# Header.net
KiCad netlist of a schematic drawn in Altium Designer
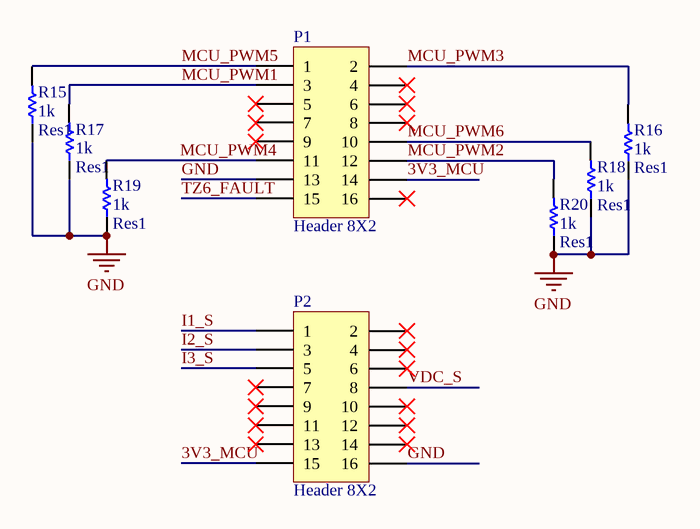
[diagram p0: Header.SchDoc]

(export (version "E")
  (design (tool "Eeschema 10.0.6"))
  (components
    (comp (ref "P1")
      (value "Header 8X2")
      (footprint "HDR2X8")
      (description "Header, 8-Pin, Dual row")
      (fields (field (name "PUBLISHER") "Altium Limited"))
      (libsource (lib "Miscellaneous Connectors") (part "Header 8X2"))
    )
    (comp (ref "P2")
      (value "Header 8X2")
      (footprint "HDR2X8")
      (description "Header, 8-Pin, Dual row")
      (fields (field (name "PUBLISHER") "Altium Limited"))
      (libsource (lib "Miscellaneous Connectors") (part "Header 8X2"))
    )
    (comp (ref "R15")
      (value "Res1")
      (footprint "AXIAL-0.4")
      (description "Resistor")
      (fields (field (name "ALTIUM_VALUE") "1k") (field (name "PUBLISHER") "Altium Limited"))
      (libsource (lib "Miscellaneous Devices") (part "Res1"))
    )
    (comp (ref "R16")
      (value "Res1")
      (footprint "AXIAL-0.4")
      (description "Resistor")
      (fields (field (name "ALTIUM_VALUE") "1k") (field (name "PUBLISHER") "Altium Limited"))
      (libsource (lib "Miscellaneous Devices") (part "Res1"))
    )
    (comp (ref "R17")
      (value "Res1")
      (footprint "AXIAL-0.4")
      (description "Resistor")
      (fields (field (name "ALTIUM_VALUE") "1k") (field (name "PUBLISHER") "Altium Limited"))
      (libsource (lib "Miscellaneous Devices") (part "Res1"))
    )
    (comp (ref "R18")
      (value "Res1")
      (footprint "AXIAL-0.4")
      (description "Resistor")
      (fields (field (name "ALTIUM_VALUE") "1k") (field (name "PUBLISHER") "Altium Limited"))
      (libsource (lib "Miscellaneous Devices") (part "Res1"))
    )
    (comp (ref "R19")
      (value "Res1")
      (footprint "AXIAL-0.4")
      (description "Resistor")
      (fields (field (name "ALTIUM_VALUE") "1k") (field (name "PUBLISHER") "Altium Limited"))
      (libsource (lib "Miscellaneous Devices") (part "Res1"))
    )
    (comp (ref "R20")
      (value "Res1")
      (footprint "AXIAL-0.4")
      (description "Resistor")
      (fields (field (name "ALTIUM_VALUE") "1k") (field (name "PUBLISHER") "Altium Limited"))
      (libsource (lib "Miscellaneous Devices") (part "Res1"))
    )
  )
  (nets
    (net (code "1") (name "/3V3_MCU") (class "Default")
      (node (ref "P1") (pin "14") (pinfunction "14_14") (pintype "passive"))
      (node (ref "P2") (pin "15") (pinfunction "15_15") (pintype "passive"))
    )
    (net (code "2") (name "/I1_S") (class "Default")
      (node (ref "P2") (pin "1") (pinfunction "1_1") (pintype "passive"))
    )
    (net (code "3") (name "/I2_S") (class "Default")
      (node (ref "P2") (pin "3") (pinfunction "3_3") (pintype "passive"))
    )
    (net (code "4") (name "/I3_S") (class "Default")
      (node (ref "P2") (pin "5") (pinfunction "5_5") (pintype "passive"))
    )
    (net (code "5") (name "/MCU_PWM1") (class "Default")
      (node (ref "P1") (pin "3") (pinfunction "3_3") (pintype "passive"))
      (node (ref "R17") (pin "2") (pinfunction "2_2") (pintype "passive"))
    )
    (net (code "6") (name "/MCU_PWM2") (class "Default")
      (node (ref "P1") (pin "12") (pinfunction "12_12") (pintype "passive"))
      (node (ref "R20") (pin "2") (pinfunction "2_2") (pintype "passive"))
    )
    (net (code "7") (name "/MCU_PWM3") (class "Default")
      (node (ref "P1") (pin "2") (pinfunction "2_2") (pintype "passive"))
      (node (ref "R16") (pin "2") (pinfunction "2_2") (pintype "passive"))
    )
    (net (code "8") (name "/MCU_PWM4") (class "Default")
      (node (ref "P1") (pin "11") (pinfunction "11_11") (pintype "passive"))
      (node (ref "R19") (pin "2") (pinfunction "2_2") (pintype "passive"))
    )
    (net (code "9") (name "/MCU_PWM5") (class "Default")
      (node (ref "P1") (pin "1") (pinfunction "1_1") (pintype "passive"))
      (node (ref "R15") (pin "2") (pinfunction "2_2") (pintype "passive"))
    )
    (net (code "10") (name "/MCU_PWM6") (class "Default")
      (node (ref "P1") (pin "10") (pinfunction "10_10") (pintype "passive"))
      (node (ref "R18") (pin "2") (pinfunction "2_2") (pintype "passive"))
    )
    (net (code "11") (name "/TZ6_FAULT") (class "Default")
      (node (ref "P1") (pin "15") (pinfunction "15_15") (pintype "passive"))
    )
    (net (code "12") (name "/VDC_S") (class "Default")
      (node (ref "P2") (pin "8") (pinfunction "8_8") (pintype "passive"))
    )
    (net (code "13") (name "GND") (class "Default")
      (node (ref "P1") (pin "13") (pinfunction "13_13") (pintype "passive"))
      (node (ref "P2") (pin "16") (pinfunction "16_16") (pintype "passive"))
      (node (ref "R15") (pin "1") (pinfunction "1_1") (pintype "passive"))
      (node (ref "R16") (pin "1") (pinfunction "1_1") (pintype "passive"))
      (node (ref "R17") (pin "1") (pinfunction "1_1") (pintype "passive"))
      (node (ref "R18") (pin "1") (pinfunction "1_1") (pintype "passive"))
      (node (ref "R19") (pin "1") (pinfunction "1_1") (pintype "passive"))
      (node (ref "R20") (pin "1") (pinfunction "1_1") (pintype "passive"))
    )
    (net (code "14") (name "unconnected-(P1-Pad4)") (class "Default")
      (node (ref "P1") (pin "4") (pinfunction "4_4") (pintype "passive+no_connect"))
    )
    (net (code "15") (name "unconnected-(P1-Pad5)") (class "Default")
      (node (ref "P1") (pin "5") (pinfunction "5_5") (pintype "passive+no_connect"))
    )
    (net (code "16") (name "unconnected-(P1-Pad6)") (class "Default")
      (node (ref "P1") (pin "6") (pinfunction "6_6") (pintype "passive+no_connect"))
    )
    (net (code "17") (name "unconnected-(P1-Pad7)") (class "Default")
      (node (ref "P1") (pin "7") (pinfunction "7_7") (pintype "passive+no_connect"))
    )
    (net (code "18") (name "unconnected-(P1-Pad8)") (class "Default")
      (node (ref "P1") (pin "8") (pinfunction "8_8") (pintype "passive+no_connect"))
    )
    (net (code "19") (name "unconnected-(P1-Pad9)") (class "Default")
      (node (ref "P1") (pin "9") (pinfunction "9_9") (pintype "passive+no_connect"))
    )
    (net (code "20") (name "unconnected-(P1-Pad16)") (class "Default")
      (node (ref "P1") (pin "16") (pinfunction "16_16") (pintype "passive+no_connect"))
    )
    (net (code "21") (name "unconnected-(P2-Pad2)") (class "Default")
      (node (ref "P2") (pin "2") (pinfunction "2_2") (pintype "passive+no_connect"))
    )
    (net (code "22") (name "unconnected-(P2-Pad4)") (class "Default")
      (node (ref "P2") (pin "4") (pinfunction "4_4") (pintype "passive+no_connect"))
    )
    (net (code "23") (name "unconnected-(P2-Pad6)") (class "Default")
      (node (ref "P2") (pin "6") (pinfunction "6_6") (pintype "passive+no_connect"))
    )
    (net (code "24") (name "unconnected-(P2-Pad7)") (class "Default")
      (node (ref "P2") (pin "7") (pinfunction "7_7") (pintype "passive+no_connect"))
    )
    (net (code "25") (name "unconnected-(P2-Pad9)") (class "Default")
      (node (ref "P2") (pin "9") (pinfunction "9_9") (pintype "passive+no_connect"))
    )
    (net (code "26") (name "unconnected-(P2-Pad10)") (class "Default")
      (node (ref "P2") (pin "10") (pinfunction "10_10") (pintype "passive+no_connect"))
    )
    (net (code "27") (name "unconnected-(P2-Pad11)") (class "Default")
      (node (ref "P2") (pin "11") (pinfunction "11_11") (pintype "passive+no_connect"))
    )
    (net (code "28") (name "unconnected-(P2-Pad12)") (class "Default")
      (node (ref "P2") (pin "12") (pinfunction "12_12") (pintype "passive+no_connect"))
    )
    (net (code "29") (name "unconnected-(P2-Pad13)") (class "Default")
      (node (ref "P2") (pin "13") (pinfunction "13_13") (pintype "passive+no_connect"))
    )
    (net (code "30") (name "unconnected-(P2-Pad14)") (class "Default")
      (node (ref "P2") (pin "14") (pinfunction "14_14") (pintype "passive+no_connect"))
    )
  )
)
